# LF.net
KiCad netlist of a schematic drawn in EAGLE
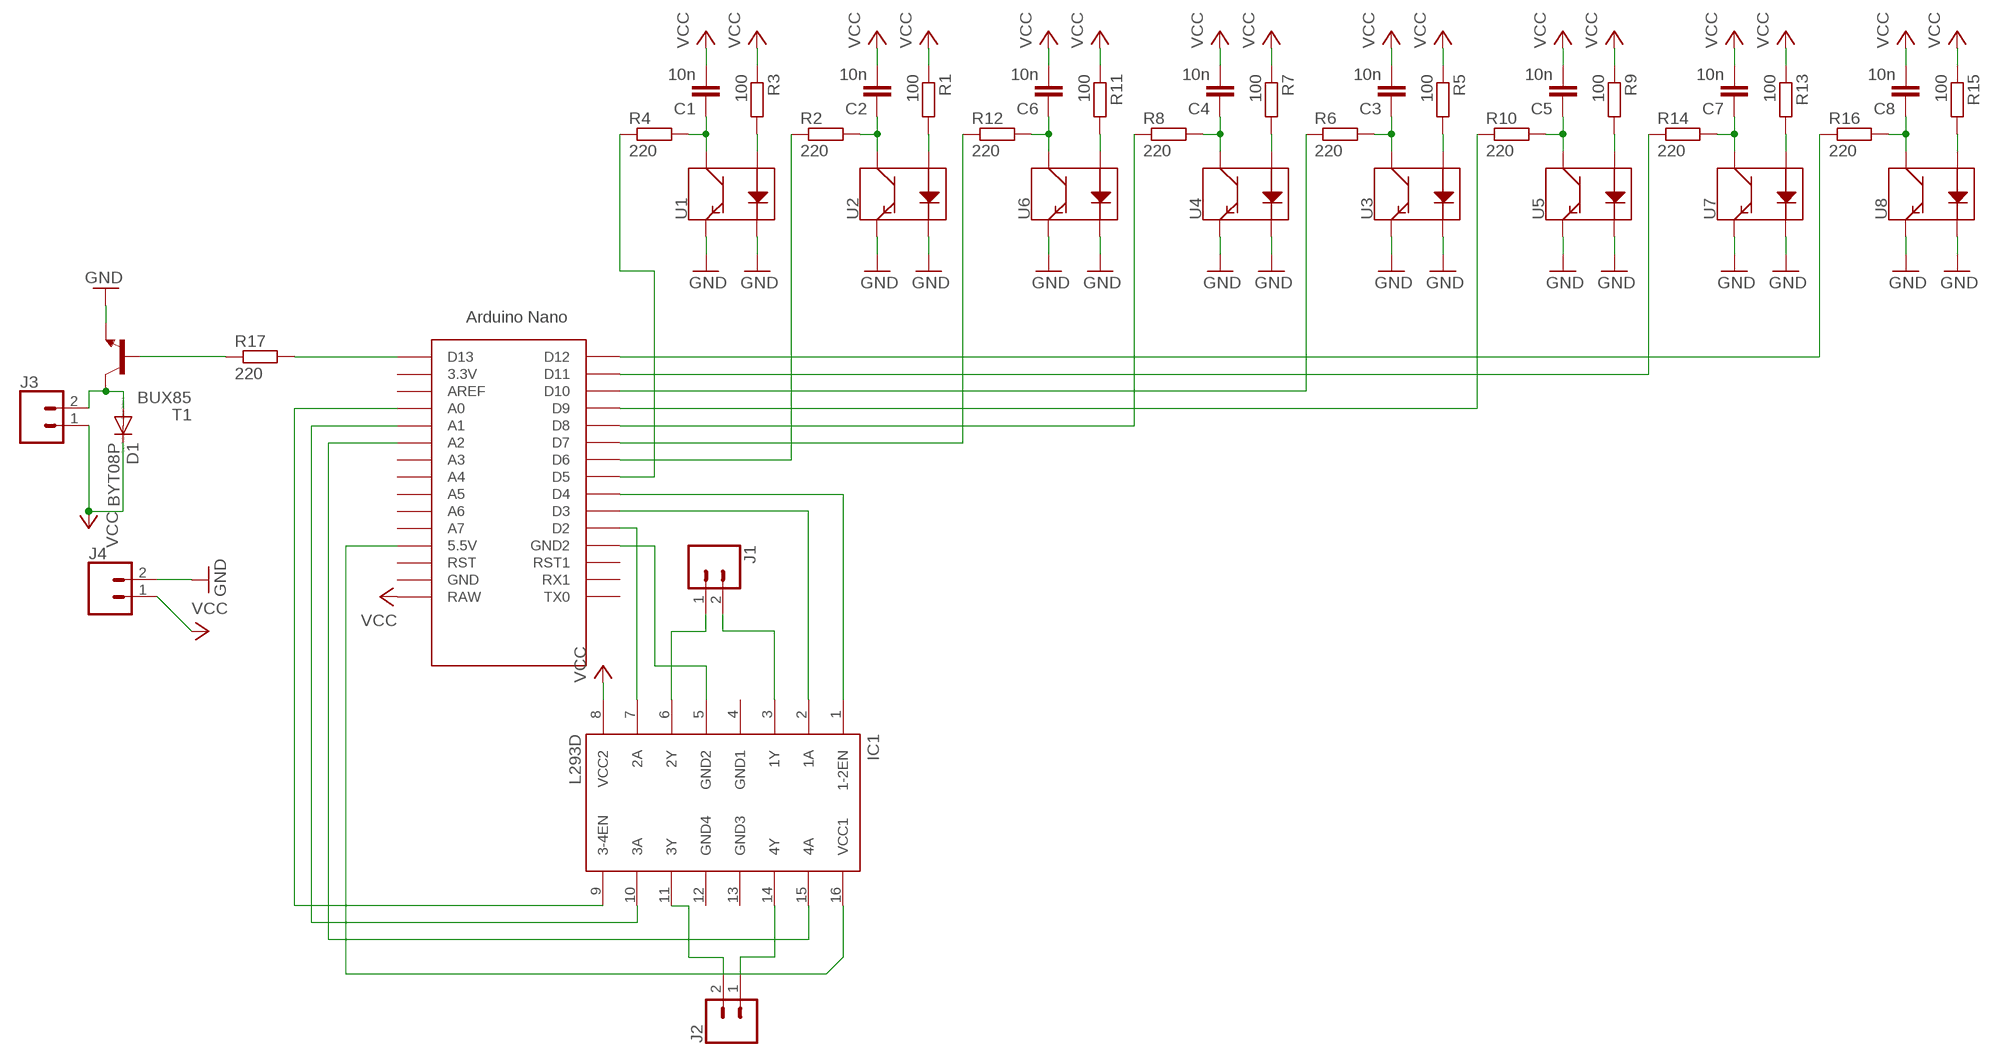
[diagram p0: schematic, sheet 1]

(export (version "E")
  (design (tool "Eeschema 10.0.6"))
  (components
    (comp (ref "C1")
      (value "10n")
      (footprint "eagle-import:C0402")
      (libsource (lib "eagle-import") (part "C-EUC0402"))
    )
    (comp (ref "C2")
      (value "10n")
      (footprint "eagle-import:C0402")
      (libsource (lib "eagle-import") (part "C-EUC0402"))
    )
    (comp (ref "C3")
      (value "10n")
      (footprint "eagle-import:C0402")
      (libsource (lib "eagle-import") (part "C-EUC0402"))
    )
    (comp (ref "C4")
      (value "10n")
      (footprint "eagle-import:C0402")
      (libsource (lib "eagle-import") (part "C-EUC0402"))
    )
    (comp (ref "C5")
      (value "10n")
      (footprint "eagle-import:C0402")
      (libsource (lib "eagle-import") (part "C-EUC0402"))
    )
    (comp (ref "C6")
      (value "10n")
      (footprint "eagle-import:C0402")
      (libsource (lib "eagle-import") (part "C-EUC0402"))
    )
    (comp (ref "C7")
      (value "10n")
      (footprint "eagle-import:C0402")
      (libsource (lib "eagle-import") (part "C-EUC0402"))
    )
    (comp (ref "C8")
      (value "10n")
      (footprint "eagle-import:C0402")
      (libsource (lib "eagle-import") (part "C-EUC0402"))
    )
    (comp (ref "D1")
      (value "BYT08P")
      (footprint "eagle-import:TO220ACS")
      (libsource (lib "eagle-import") (part "BYT08P"))
    )
    (comp (ref "IC1")
      (value "L293D")
      (footprint "eagle-import:DIL16")
      (libsource (lib "eagle-import") (part "L293D"))
    )
    (comp (ref "J1")
      (value "CONN_02")
      (footprint "eagle-import:1X02")
      (libsource (lib "eagle-import") (part "CONN_02"))
    )
    (comp (ref "J2")
      (value "CONN_02")
      (footprint "eagle-import:1X02")
      (libsource (lib "eagle-import") (part "CONN_02"))
    )
    (comp (ref "J3")
      (value "CONN_02")
      (footprint "eagle-import:1X02")
      (libsource (lib "eagle-import") (part "CONN_02"))
    )
    (comp (ref "J4")
      (value "CONN_02")
      (footprint "eagle-import:1X02")
      (libsource (lib "eagle-import") (part "CONN_02"))
    )
    (comp (ref "R1")
      (value "100")
      (footprint "eagle-import:R0402")
      (libsource (lib "eagle-import") (part "R-EU_R0402"))
    )
    (comp (ref "R2")
      (value "220")
      (footprint "eagle-import:R0402")
      (libsource (lib "eagle-import") (part "R-EU_R0402"))
    )
    (comp (ref "R3")
      (value "100")
      (footprint "eagle-import:R0402")
      (libsource (lib "eagle-import") (part "R-EU_R0402"))
    )
    (comp (ref "R4")
      (value "220")
      (footprint "eagle-import:R0402")
      (libsource (lib "eagle-import") (part "R-EU_R0402"))
    )
    (comp (ref "R5")
      (value "100")
      (footprint "eagle-import:R0402")
      (libsource (lib "eagle-import") (part "R-EU_R0402"))
    )
    (comp (ref "R6")
      (value "220")
      (footprint "eagle-import:R0402")
      (libsource (lib "eagle-import") (part "R-EU_R0402"))
    )
    (comp (ref "R7")
      (value "100")
      (footprint "eagle-import:R0402")
      (libsource (lib "eagle-import") (part "R-EU_R0402"))
    )
    (comp (ref "R8")
      (value "220")
      (footprint "eagle-import:R0402")
      (libsource (lib "eagle-import") (part "R-EU_R0402"))
    )
    (comp (ref "R9")
      (value "100")
      (footprint "eagle-import:R0402")
      (libsource (lib "eagle-import") (part "R-EU_R0402"))
    )
    (comp (ref "R10")
      (value "220")
      (footprint "eagle-import:R0402")
      (libsource (lib "eagle-import") (part "R-EU_R0402"))
    )
    (comp (ref "R11")
      (value "100")
      (footprint "eagle-import:R0402")
      (libsource (lib "eagle-import") (part "R-EU_R0402"))
    )
    (comp (ref "R12")
      (value "220")
      (footprint "eagle-import:R0402")
      (libsource (lib "eagle-import") (part "R-EU_R0402"))
    )
    (comp (ref "R13")
      (value "100")
      (footprint "eagle-import:R0402")
      (libsource (lib "eagle-import") (part "R-EU_R0402"))
    )
    (comp (ref "R14")
      (value "220")
      (footprint "eagle-import:R0402")
      (libsource (lib "eagle-import") (part "R-EU_R0402"))
    )
    (comp (ref "R15")
      (value "100")
      (footprint "eagle-import:R0402")
      (libsource (lib "eagle-import") (part "R-EU_R0402"))
    )
    (comp (ref "R16")
      (value "220")
      (footprint "eagle-import:R0402")
      (libsource (lib "eagle-import") (part "R-EU_R0402"))
    )
    (comp (ref "R17")
      (value "220")
      (footprint "eagle-import:R1206")
      (libsource (lib "eagle-import") (part "R-EU_R1206"))
    )
    (comp (ref "T1")
      (value "BUX85")
      (footprint "eagle-import:TO220")
      (libsource (lib "eagle-import") (part "BUX85"))
    )
    (comp (ref "U$1")
      (value "NANO")
      (footprint "eagle-import:NANO")
      (libsource (lib "eagle-import") (part "NANO"))
    )
    (comp (ref "U1")
      (value "QRE1113SMD-W")
      (footprint "eagle-import:QRE1113-W")
      (libsource (lib "eagle-import") (part "QRE1113SMD-W"))
    )
    (comp (ref "U2")
      (value "QRE1113SMD-W")
      (footprint "eagle-import:QRE1113-W")
      (libsource (lib "eagle-import") (part "QRE1113SMD-W"))
    )
    (comp (ref "U3")
      (value "QRE1113SMD-W")
      (footprint "eagle-import:QRE1113-W")
      (libsource (lib "eagle-import") (part "QRE1113SMD-W"))
    )
    (comp (ref "U4")
      (value "QRE1113SMD-W")
      (footprint "eagle-import:QRE1113-W")
      (libsource (lib "eagle-import") (part "QRE1113SMD-W"))
    )
    (comp (ref "U5")
      (value "QRE1113SMD-W")
      (footprint "eagle-import:QRE1113-W")
      (libsource (lib "eagle-import") (part "QRE1113SMD-W"))
    )
    (comp (ref "U6")
      (value "QRE1113SMD-W")
      (footprint "eagle-import:QRE1113-W")
      (libsource (lib "eagle-import") (part "QRE1113SMD-W"))
    )
    (comp (ref "U7")
      (value "QRE1113SMD-W")
      (footprint "eagle-import:QRE1113-W")
      (libsource (lib "eagle-import") (part "QRE1113SMD-W"))
    )
    (comp (ref "U8")
      (value "QRE1113SMD-W")
      (footprint "eagle-import:QRE1113-W")
      (libsource (lib "eagle-import") (part "QRE1113SMD-W"))
    )
  )
  (nets
    (net (code "1") (name "/GND1") (class "Default")
      (node (ref "IC1") (pin "4") (pinfunction "GND1_4") (pintype "power_in"))
    )
    (net (code "2") (name "/GND3") (class "Default")
      (node (ref "IC1") (pin "13") (pinfunction "GND3_13") (pintype "power_in"))
    )
    (net (code "3") (name "/GND4") (class "Default")
      (node (ref "IC1") (pin "12") (pinfunction "GND4_12") (pintype "power_in"))
    )
    (net (code "4") (name "GND") (class "Default")
      (node (ref "J4") (pin "2") (pinfunction "2_2") (pintype "passive"))
      (node (ref "T1") (pin "3") (pinfunction "E_3") (pintype "passive"))
      (node (ref "U1") (pin "2") (pinfunction "K_2") (pintype "bidirectional"))
      (node (ref "U1") (pin "4") (pinfunction "E_4") (pintype "bidirectional"))
      (node (ref "U2") (pin "2") (pinfunction "K_2") (pintype "bidirectional"))
      (node (ref "U2") (pin "4") (pinfunction "E_4") (pintype "bidirectional"))
      (node (ref "U3") (pin "2") (pinfunction "K_2") (pintype "bidirectional"))
      (node (ref "U3") (pin "4") (pinfunction "E_4") (pintype "bidirectional"))
      (node (ref "U4") (pin "2") (pinfunction "K_2") (pintype "bidirectional"))
      (node (ref "U4") (pin "4") (pinfunction "E_4") (pintype "bidirectional"))
      (node (ref "U5") (pin "2") (pinfunction "K_2") (pintype "bidirectional"))
      (node (ref "U5") (pin "4") (pinfunction "E_4") (pintype "bidirectional"))
      (node (ref "U6") (pin "2") (pinfunction "K_2") (pintype "bidirectional"))
      (node (ref "U6") (pin "4") (pinfunction "E_4") (pintype "bidirectional"))
      (node (ref "U7") (pin "2") (pinfunction "K_2") (pintype "bidirectional"))
      (node (ref "U7") (pin "4") (pinfunction "E_4") (pintype "bidirectional"))
      (node (ref "U8") (pin "2") (pinfunction "K_2") (pintype "bidirectional"))
      (node (ref "U8") (pin "4") (pinfunction "E_4") (pintype "bidirectional"))
    )
    (net (code "5") (name "Net-(IC1-1-2EN)") (class "Default")
      (node (ref "IC1") (pin "1") (pinfunction "1-2EN_1") (pintype "input"))
      (node (ref "U$1") (pin "D4") (pinfunction "D4_D4") (pintype "bidirectional"))
    )
    (net (code "6") (name "Net-(IC1-1A)") (class "Default")
      (node (ref "IC1") (pin "2") (pinfunction "1A_2") (pintype "input"))
      (node (ref "U$1") (pin "D3") (pinfunction "D3_D3") (pintype "bidirectional"))
    )
    (net (code "7") (name "Net-(IC1-1Y)") (class "Default")
      (node (ref "IC1") (pin "3") (pinfunction "1Y_3") (pintype "output"))
      (node (ref "J1") (pin "2") (pinfunction "2_2") (pintype "passive"))
    )
    (net (code "8") (name "Net-(IC1-2A)") (class "Default")
      (node (ref "IC1") (pin "7") (pinfunction "2A_7") (pintype "input"))
      (node (ref "U$1") (pin "D2") (pinfunction "D2_D2") (pintype "bidirectional"))
    )
    (net (code "9") (name "Net-(IC1-2Y)") (class "Default")
      (node (ref "IC1") (pin "6") (pinfunction "2Y_6") (pintype "output"))
      (node (ref "J1") (pin "1") (pinfunction "1_1") (pintype "passive"))
    )
    (net (code "10") (name "Net-(IC1-3-4EN)") (class "Default")
      (node (ref "IC1") (pin "9") (pinfunction "3-4EN_9") (pintype "input"))
      (node (ref "U$1") (pin "A0") (pinfunction "A0_A0") (pintype "bidirectional"))
    )
    (net (code "11") (name "Net-(IC1-3A)") (class "Default")
      (node (ref "IC1") (pin "10") (pinfunction "3A_10") (pintype "input"))
      (node (ref "U$1") (pin "A1") (pinfunction "A1_A1") (pintype "bidirectional"))
    )
    (net (code "12") (name "Net-(IC1-3Y)") (class "Default")
      (node (ref "IC1") (pin "11") (pinfunction "3Y_11") (pintype "output"))
      (node (ref "J2") (pin "2") (pinfunction "2_2") (pintype "passive"))
    )
    (net (code "13") (name "Net-(IC1-4A)") (class "Default")
      (node (ref "IC1") (pin "15") (pinfunction "4A_15") (pintype "input"))
      (node (ref "U$1") (pin "A2") (pinfunction "A2_A2") (pintype "bidirectional"))
    )
    (net (code "14") (name "Net-(IC1-4Y)") (class "Default")
      (node (ref "IC1") (pin "14") (pinfunction "4Y_14") (pintype "output"))
      (node (ref "J2") (pin "1") (pinfunction "1_1") (pintype "passive"))
    )
    (net (code "15") (name "Net-(IC1-GND2)") (class "Default")
      (node (ref "IC1") (pin "5") (pinfunction "GND2_5") (pintype "power_in"))
      (node (ref "U$1") (pin "GND1") (pinfunction "GND2_GND1") (pintype "bidirectional"))
    )
    (net (code "16") (name "Net-(IC1-VCC1)") (class "Default")
      (node (ref "IC1") (pin "16") (pinfunction "VCC1_16") (pintype "power_in"))
      (node (ref "U$1") (pin "5V") (pinfunction "5.5V_5V") (pintype "bidirectional"))
    )
    (net (code "17") (name "Net-(R2-Pad1)") (class "Default")
      (node (ref "R2") (pin "1") (pinfunction "1_1") (pintype "passive"))
      (node (ref "U$1") (pin "D6") (pinfunction "D6_D6") (pintype "bidirectional"))
    )
    (net (code "18") (name "Net-(R4-Pad1)") (class "Default")
      (node (ref "R4") (pin "1") (pinfunction "1_1") (pintype "passive"))
      (node (ref "U$1") (pin "D5") (pinfunction "D5_D5") (pintype "bidirectional"))
    )
    (net (code "19") (name "Net-(R6-Pad1)") (class "Default")
      (node (ref "R6") (pin "1") (pinfunction "1_1") (pintype "passive"))
      (node (ref "U$1") (pin "D10") (pinfunction "D10_D10") (pintype "bidirectional"))
    )
    (net (code "20") (name "Net-(R8-Pad1)") (class "Default")
      (node (ref "R8") (pin "1") (pinfunction "1_1") (pintype "passive"))
      (node (ref "U$1") (pin "D8") (pinfunction "D8_D8") (pintype "bidirectional"))
    )
    (net (code "21") (name "Net-(R10-Pad1)") (class "Default")
      (node (ref "R10") (pin "1") (pinfunction "1_1") (pintype "passive"))
      (node (ref "U$1") (pin "D9") (pinfunction "D9_D9") (pintype "bidirectional"))
    )
    (net (code "22") (name "Net-(R12-Pad1)") (class "Default")
      (node (ref "R12") (pin "1") (pinfunction "1_1") (pintype "passive"))
      (node (ref "U$1") (pin "D7") (pinfunction "D7_D7") (pintype "bidirectional"))
    )
    (net (code "23") (name "Net-(R14-Pad1)") (class "Default")
      (node (ref "R14") (pin "1") (pinfunction "1_1") (pintype "passive"))
      (node (ref "U$1") (pin "D11") (pinfunction "D11_D11") (pintype "bidirectional"))
    )
    (net (code "24") (name "Net-(R16-Pad1)") (class "Default")
      (node (ref "R16") (pin "1") (pinfunction "1_1") (pintype "passive"))
      (node (ref "U$1") (pin "D12") (pinfunction "D12_D12") (pintype "bidirectional"))
    )
    (net (code "25") (name "Net-(R17-Pad2)") (class "Default")
      (node (ref "R17") (pin "2") (pinfunction "2_2") (pintype "passive"))
      (node (ref "U$1") (pin "D13") (pinfunction "D13_D13") (pintype "bidirectional"))
    )
    (net (code "26") (name "Net-(T1-B)") (class "Default")
      (node (ref "R17") (pin "1") (pinfunction "1_1") (pintype "passive"))
      (node (ref "T1") (pin "1") (pinfunction "B_1") (pintype "passive"))
    )
    (net (code "27") (name "Net-(T1-C)") (class "Default")
      (node (ref "D1") (pin "A") (pinfunction "A_A") (pintype "passive"))
      (node (ref "J3") (pin "2") (pinfunction "2_2") (pintype "passive"))
      (node (ref "T1") (pin "2") (pinfunction "C_2") (pintype "passive"))
    )
    (net (code "28") (name "Net-(U1-A)") (class "Default")
      (node (ref "R3") (pin "2") (pinfunction "2_2") (pintype "passive"))
      (node (ref "U1") (pin "1") (pinfunction "A_1") (pintype "bidirectional"))
    )
    (net (code "29") (name "Net-(U1-C)") (class "Default")
      (node (ref "C1") (pin "1") (pinfunction "1_1") (pintype "passive"))
      (node (ref "R4") (pin "2") (pinfunction "2_2") (pintype "passive"))
      (node (ref "U1") (pin "3") (pinfunction "C_3") (pintype "bidirectional"))
    )
    (net (code "30") (name "Net-(U2-A)") (class "Default")
      (node (ref "R1") (pin "2") (pinfunction "2_2") (pintype "passive"))
      (node (ref "U2") (pin "1") (pinfunction "A_1") (pintype "bidirectional"))
    )
    (net (code "31") (name "Net-(U2-C)") (class "Default")
      (node (ref "C2") (pin "1") (pinfunction "1_1") (pintype "passive"))
      (node (ref "R2") (pin "2") (pinfunction "2_2") (pintype "passive"))
      (node (ref "U2") (pin "3") (pinfunction "C_3") (pintype "bidirectional"))
    )
    (net (code "32") (name "Net-(U3-A)") (class "Default")
      (node (ref "R5") (pin "2") (pinfunction "2_2") (pintype "passive"))
      (node (ref "U3") (pin "1") (pinfunction "A_1") (pintype "bidirectional"))
    )
    (net (code "33") (name "Net-(U3-C)") (class "Default")
      (node (ref "C3") (pin "1") (pinfunction "1_1") (pintype "passive"))
      (node (ref "R6") (pin "2") (pinfunction "2_2") (pintype "passive"))
      (node (ref "U3") (pin "3") (pinfunction "C_3") (pintype "bidirectional"))
    )
    (net (code "34") (name "Net-(U4-A)") (class "Default")
      (node (ref "R7") (pin "2") (pinfunction "2_2") (pintype "passive"))
      (node (ref "U4") (pin "1") (pinfunction "A_1") (pintype "bidirectional"))
    )
    (net (code "35") (name "Net-(U4-C)") (class "Default")
      (node (ref "C4") (pin "1") (pinfunction "1_1") (pintype "passive"))
      (node (ref "R8") (pin "2") (pinfunction "2_2") (pintype "passive"))
      (node (ref "U4") (pin "3") (pinfunction "C_3") (pintype "bidirectional"))
    )
    (net (code "36") (name "Net-(U5-A)") (class "Default")
      (node (ref "R9") (pin "2") (pinfunction "2_2") (pintype "passive"))
      (node (ref "U5") (pin "1") (pinfunction "A_1") (pintype "bidirectional"))
    )
    (net (code "37") (name "Net-(U5-C)") (class "Default")
      (node (ref "C5") (pin "1") (pinfunction "1_1") (pintype "passive"))
      (node (ref "R10") (pin "2") (pinfunction "2_2") (pintype "passive"))
      (node (ref "U5") (pin "3") (pinfunction "C_3") (pintype "bidirectional"))
    )
    (net (code "38") (name "Net-(U6-A)") (class "Default")
      (node (ref "R11") (pin "2") (pinfunction "2_2") (pintype "passive"))
      (node (ref "U6") (pin "1") (pinfunction "A_1") (pintype "bidirectional"))
    )
    (net (code "39") (name "Net-(U6-C)") (class "Default")
      (node (ref "C6") (pin "1") (pinfunction "1_1") (pintype "passive"))
      (node (ref "R12") (pin "2") (pinfunction "2_2") (pintype "passive"))
      (node (ref "U6") (pin "3") (pinfunction "C_3") (pintype "bidirectional"))
    )
    (net (code "40") (name "Net-(U7-A)") (class "Default")
      (node (ref "R13") (pin "2") (pinfunction "2_2") (pintype "passive"))
      (node (ref "U7") (pin "1") (pinfunction "A_1") (pintype "bidirectional"))
    )
    (net (code "41") (name "Net-(U7-C)") (class "Default")
      (node (ref "C7") (pin "1") (pinfunction "1_1") (pintype "passive"))
      (node (ref "R14") (pin "2") (pinfunction "2_2") (pintype "passive"))
      (node (ref "U7") (pin "3") (pinfunction "C_3") (pintype "bidirectional"))
    )
    (net (code "42") (name "Net-(U8-A)") (class "Default")
      (node (ref "R15") (pin "2") (pinfunction "2_2") (pintype "passive"))
      (node (ref "U8") (pin "1") (pinfunction "A_1") (pintype "bidirectional"))
    )
    (net (code "43") (name "Net-(U8-C)") (class "Default")
      (node (ref "C8") (pin "1") (pinfunction "1_1") (pintype "passive"))
      (node (ref "R16") (pin "2") (pinfunction "2_2") (pintype "passive"))
      (node (ref "U8") (pin "3") (pinfunction "C_3") (pintype "bidirectional"))
    )
    (net (code "44") (name "VCC") (class "Default")
      (node (ref "C1") (pin "2") (pinfunction "2_2") (pintype "passive"))
      (node (ref "C2") (pin "2") (pinfunction "2_2") (pintype "passive"))
      (node (ref "C3") (pin "2") (pinfunction "2_2") (pintype "passive"))
      (node (ref "C4") (pin "2") (pinfunction "2_2") (pintype "passive"))
      (node (ref "C5") (pin "2") (pinfunction "2_2") (pintype "passive"))
      (node (ref "C6") (pin "2") (pinfunction "2_2") (pintype "passive"))
      (node (ref "C7") (pin "2") (pinfunction "2_2") (pintype "passive"))
      (node (ref "C8") (pin "2") (pinfunction "2_2") (pintype "passive"))
      (node (ref "D1") (pin "C") (pinfunction "C_C") (pintype "passive"))
      (node (ref "IC1") (pin "8") (pinfunction "VCC2_8") (pintype "power_in"))
      (node (ref "J3") (pin "1") (pinfunction "1_1") (pintype "passive"))
      (node (ref "J4") (pin "1") (pinfunction "1_1") (pintype "passive"))
      (node (ref "R1") (pin "1") (pinfunction "1_1") (pintype "passive"))
      (node (ref "R11") (pin "1") (pinfunction "1_1") (pintype "passive"))
      (node (ref "R13") (pin "1") (pinfunction "1_1") (pintype "passive"))
      (node (ref "R15") (pin "1") (pinfunction "1_1") (pintype "passive"))
      (node (ref "R3") (pin "1") (pinfunction "1_1") (pintype "passive"))
      (node (ref "R5") (pin "1") (pinfunction "1_1") (pintype "passive"))
      (node (ref "R7") (pin "1") (pinfunction "1_1") (pintype "passive"))
      (node (ref "R9") (pin "1") (pinfunction "1_1") (pintype "passive"))
      (node (ref "U$1") (pin "RAW") (pinfunction "RAW_RAW") (pintype "bidirectional"))
    )
    (net (code "45") (name "unconnected-(U$1-Pad3.3V)") (class "Default")
      (node (ref "U$1") (pin "3.3V") (pinfunction "3.3V_3.3V") (pintype "bidirectional"))
    )
    (net (code "46") (name "unconnected-(U$1-PadA3)") (class "Default")
      (node (ref "U$1") (pin "A3") (pinfunction "A3_A3") (pintype "bidirectional"))
    )
    (net (code "47") (name "unconnected-(U$1-PadA4)") (class "Default")
      (node (ref "U$1") (pin "A4") (pinfunction "A4_A4") (pintype "bidirectional"))
    )
    (net (code "48") (name "unconnected-(U$1-PadA5)") (class "Default")
      (node (ref "U$1") (pin "A5") (pinfunction "A5_A5") (pintype "bidirectional"))
    )
    (net (code "49") (name "unconnected-(U$1-PadA6)") (class "Default")
      (node (ref "U$1") (pin "A6") (pinfunction "A6_A6") (pintype "bidirectional"))
    )
    (net (code "50") (name "unconnected-(U$1-PadA7)") (class "Default")
      (node (ref "U$1") (pin "A7") (pinfunction "A7_A7") (pintype "bidirectional"))
    )
    (net (code "51") (name "unconnected-(U$1-PadAREF)") (class "Default")
      (node (ref "U$1") (pin "AREF") (pinfunction "AREF_AREF") (pintype "bidirectional"))
    )
    (net (code "52") (name "unconnected-(U$1-PadGND)") (class "Default")
      (node (ref "U$1") (pin "GND") (pinfunction "GND_GND") (pintype "bidirectional"))
    )
    (net (code "53") (name "unconnected-(U$1-PadICSP1)") (class "Default")
      (node (ref "U$1") (pin "ICSP1") (pinfunction "ICSP1_ICSP1") (pintype "bidirectional"))
    )
    (net (code "54") (name "unconnected-(U$1-PadICSP2)") (class "Default")
      (node (ref "U$1") (pin "ICSP2") (pinfunction "ICSP2_ICSP2") (pintype "bidirectional"))
    )
    (net (code "55") (name "unconnected-(U$1-PadICSP3)") (class "Default")
      (node (ref "U$1") (pin "ICSP3") (pinfunction "ICSP3_ICSP3") (pintype "bidirectional"))
    )
    (net (code "56") (name "unconnected-(U$1-PadICSP4)") (class "Default")
      (node (ref "U$1") (pin "ICSP4") (pinfunction "ICSP4_ICSP4") (pintype "bidirectional"))
    )
    (net (code "57") (name "unconnected-(U$1-PadICSP5)") (class "Default")
      (node (ref "U$1") (pin "ICSP5") (pinfunction "ICSP5_ICSP5") (pintype "bidirectional"))
    )
    (net (code "58") (name "unconnected-(U$1-PadICSP6)") (class "Default")
      (node (ref "U$1") (pin "ICSP6") (pinfunction "ICSP6_ICSP6") (pintype "bidirectional"))
    )
    (net (code "59") (name "unconnected-(U$1-PadRST)") (class "Default")
      (node (ref "U$1") (pin "RST") (pinfunction "RST_RST") (pintype "bidirectional"))
    )
    (net (code "60") (name "unconnected-(U$1-PadRST1)") (class "Default")
      (node (ref "U$1") (pin "RST1") (pinfunction "RST1_RST1") (pintype "bidirectional"))
    )
    (net (code "61") (name "unconnected-(U$1-PadRX1)") (class "Default")
      (node (ref "U$1") (pin "RX1") (pinfunction "RX1_RX1") (pintype "bidirectional"))
    )
    (net (code "62") (name "unconnected-(U$1-PadTX0)") (class "Default")
      (node (ref "U$1") (pin "TX0") (pinfunction "TX0_TX0") (pintype "bidirectional"))
    )
  )
)
